# design.net
KiCad netlist of a schematic drawn in Altium Designer
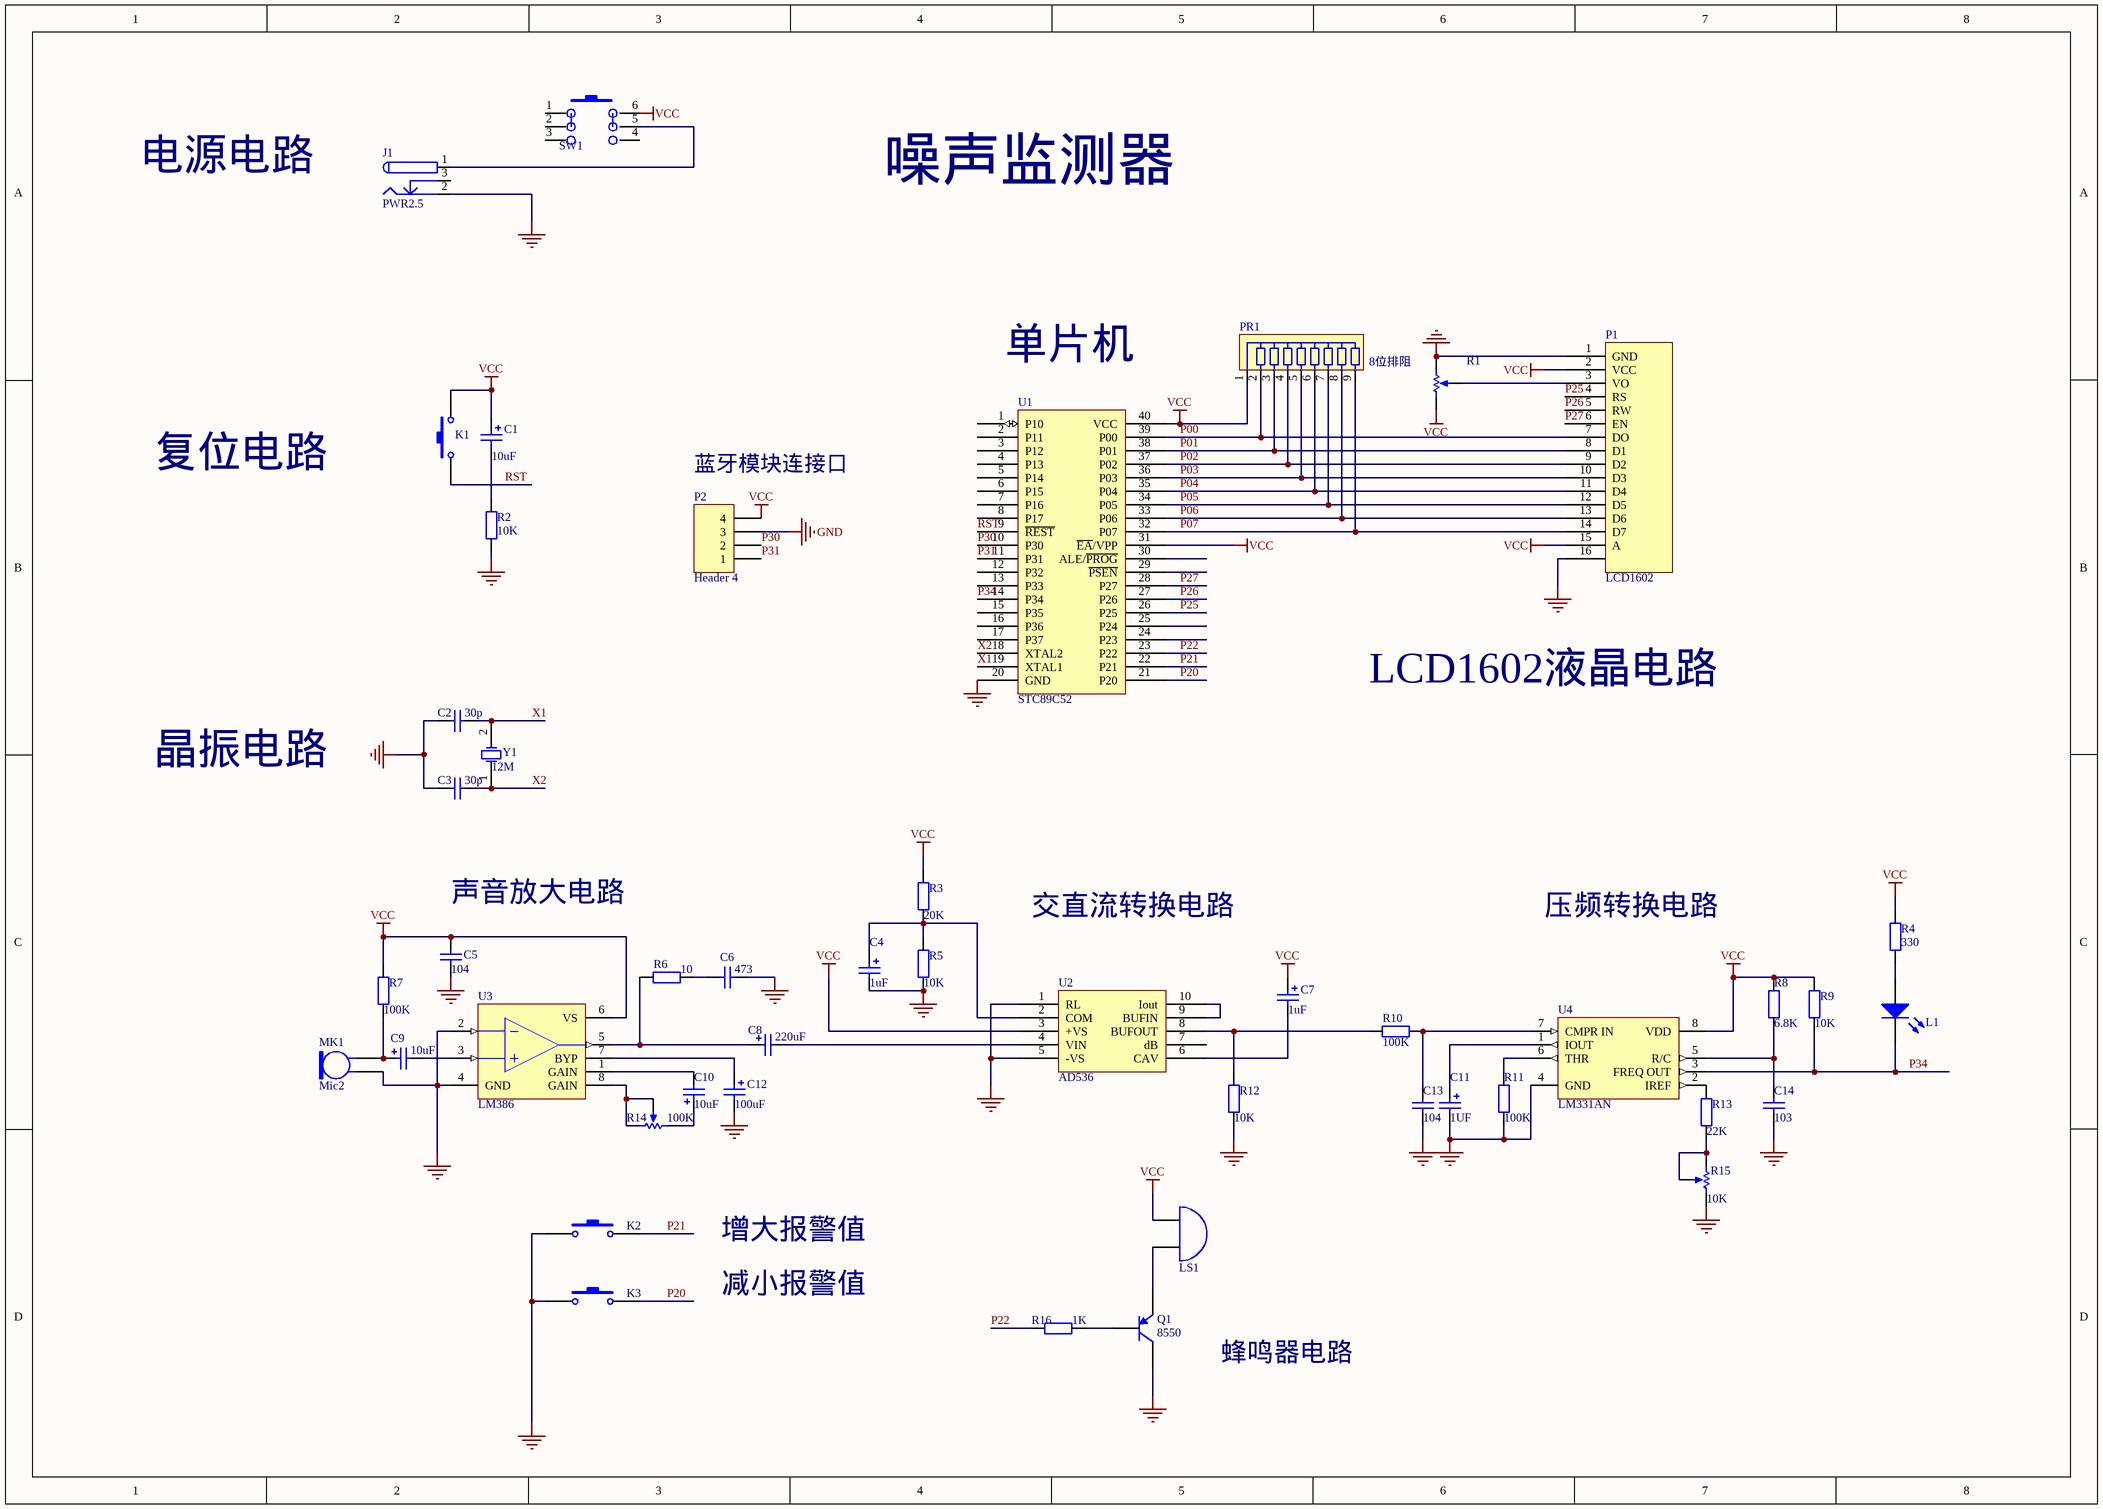
[diagram p0: 噪声监测器.SchDoc]

(export (version "E")
  (design (tool "Eeschema 10.0.6"))
  (components
    (comp (ref "C1") (value "10uF") (footprint "CAP2") (libsource (lib "*") (part "C+")))
    (comp (ref "C2") (value "30p") (footprint "CAPNORM") (libsource (lib "*") (part "CAP")))
    (comp (ref "C3") (value "30p") (footprint "CAPNORM") (libsource (lib "*") (part "CAP")))
    (comp (ref "C4") (value "1uF") (footprint "CAP3") (libsource (lib "*") (part "C+")))
    (comp (ref "C5") (value "104") (footprint "CAPNORM") (libsource (lib "*") (part "CAP")))
    (comp (ref "C6") (value "473") (footprint "CAPNORM") (libsource (lib "*") (part "CAP")))
    (comp (ref "C7") (value "1uF") (footprint "CAP3") (libsource (lib "*") (part "C+")))
    (comp (ref "C8") (value "220uF") (footprint "CAP4") (libsource (lib "*") (part "C+")))
    (comp (ref "C9") (value "10uF") (footprint "CAP2") (libsource (lib "*") (part "C+")))
    (comp (ref "C10") (value "10uF") (footprint "CAP2") (libsource (lib "*") (part "C+")))
    (comp (ref "C11") (value "1UF") (footprint "CAP2") (libsource (lib "*") (part "C+")))
    (comp (ref "C12") (value "100uF") (footprint "CAP3") (libsource (lib "*") (part "C+")))
    (comp (ref "C13") (value "104") (footprint "CAPNORM") (libsource (lib "*") (part "CAP")))
    (comp (ref "C14") (value "103") (footprint "CAPNORM") (libsource (lib "*") (part "CAP")))
    (comp (ref "J1")
      (value "PWR2.5")
      (footprint "PWR5V")
      (description "Low Voltage Power Supply Connector")
      (fields (field (name "PUBLISHER") "Altium Limited"))
      (libsource (lib "*") (part "PWR2.5"))
    )
    (comp (ref "K1") (value "SW-AJ") (footprint "KaiGuan") (libsource (lib "*") (part "SW-AJ")))
    (comp (ref "K2") (value "SW-AJ") (footprint "KaiGuan") (libsource (lib "*") (part "SW-AJ")))
    (comp (ref "K3") (value "SW-AJ") (footprint "KaiGuan") (libsource (lib "*") (part "SW-AJ")))
    (comp (ref "L1") (value "LED") (footprint "LED") (libsource (lib "*") (part "LED")))
    (comp (ref "LS1")
      (value "Bell")
      (footprint "FengMing")
      (description "Electrical Bell")
      (fields (field (name "MANUFACTURER") "Generic Components"))
      (libsource (lib "*") (part "Bell"))
    )
    (comp (ref "MK1")
      (value "Mic2")
      (footprint "MK1")
      (description "Microphone")
      (fields (field (name "PUBLISHER") "Altium Limited"))
      (libsource (lib "*") (part "Mic2"))
    )
    (comp (ref "P1") (value "LCD1602") (footprint "1602") (libsource (lib "*") (part "LCD1602")))
    (comp (ref "P2")
      (value "Header 4")
      (footprint "HT396K-4")
      (description "Header, 4-Pin")
      (fields (field (name "PUBLISHER") "Altium Limited"))
      (libsource (lib "01 Connect_IntegratedLibrary") (part "Header 4"))
    )
    (comp (ref "PR1") (value "8位排阻") (footprint "HDR1X9") (libsource (lib "*") (part "8位排阻")))
    (comp (ref "Q1")
      (value "8550")
      (footprint "SANJIGUAN")
      (description "PNP General Purpose Amplifier")
      (fields (field (name "PUBLISHER") "Altium Limited"))
      (libsource (lib "*") (part "2N3906"))
    )
    (comp (ref "R1")
      (value "~")
      (footprint "DIANWEIQI")
      (description "Potentiometer")
      (fields (field (name "PUBLISHER") "Altium Limited"))
      (libsource (lib "*") (part "RPot"))
    )
    (comp (ref "R2")
      (value "10K")
      (footprint "AXIAL-0.3")
      (description "Resistor")
      (fields (field (name "PUBLISHER") "Altium Limited"))
      (libsource (lib "") (part "Res2_1"))
    )
    (comp (ref "R3") (value "20K") (footprint "AXIAL-0.3") (libsource (lib "*") (part "RES0.4")))
    (comp (ref "R4")
      (value "330")
      (footprint "AXIAL-0.3")
      (description "Resistor")
      (fields (field (name "PUBLISHER") "Altium Limited"))
      (libsource (lib "*") (part "Res2"))
    )
    (comp (ref "R5") (value "10K") (footprint "AXIAL-0.3") (libsource (lib "*") (part "RES0.4")))
    (comp (ref "R6") (value "10") (footprint "AXIAL-0.3") (libsource (lib "") (part "RES0.4_1")))
    (comp (ref "R7") (value "100K") (footprint "AXIAL-0.3") (libsource (lib "") (part "RES0.4_2")))
    (comp (ref "R8") (value "6.8K") (footprint "AXIAL-0.3") (libsource (lib "") (part "电阻_2")))
    (comp (ref "R9") (value "10K") (footprint "AXIAL-0.3") (libsource (lib "") (part "电阻_1")))
    (comp (ref "R10") (value "100K") (footprint "AXIAL-0.3") (libsource (lib "*") (part "电阻")))
    (comp (ref "R11") (value "100K") (footprint "AXIAL-0.3") (libsource (lib "") (part "电阻_1")))
    (comp (ref "R12") (value "10K") (footprint "AXIAL-0.3") (libsource (lib "*") (part "RES0.4")))
    (comp (ref "R13") (value "22K") (footprint "AXIAL-0.3") (libsource (lib "") (part "电阻_2")))
    (comp (ref "R14")
      (value "100K")
      (footprint "Bianzuqi")
      (description "Potentiometer")
      (fields (field (name "PUBLISHER") "Altium Limited"))
      (libsource (lib "*") (part "RPot"))
    )
    (comp (ref "R15")
      (value "10K")
      (footprint "Bianzuqi")
      (description "Potentiometer")
      (fields (field (name "PUBLISHER") "Altium Limited"))
      (libsource (lib "*") (part "RPot"))
    )
    (comp (ref "R16")
      (value "1K")
      (footprint "AXIAL-0.3")
      (description "Resistor")
      (fields (field (name "PUBLISHER") "Altium Limited"))
      (libsource (lib "") (part "Res2_2"))
    )
    (comp (ref "SW1") (value "SW-6P") (footprint "SW-6P") (libsource (lib "6开关蜂鸣器电池等") (part "SW-6P")))
    (comp (ref "U1") (value "STC89C52") (footprint "52DANPIANJi") (libsource (lib "*") (part "AT89S52_1")))
    (comp (ref "U2") (value "AD536") (footprint "AD536") (libsource (lib "*") (part "AD536A")))
    (comp (ref "U3")
      (value "LM386")
      (footprint "LM386")
      (description "Low-Voltage Audio Power Amplifier")
      (fields (field (name "PUBLISHER") "Altium Limited"))
      (libsource (lib "*") (part "LM386M-1"))
    )
    (comp (ref "U4")
      (value "LM331AN")
      (footprint "LM331AN")
      (description "Precision Voltage-to-Frequency Converter")
      (fields (field (name "PUBLISHER") "Altium Limited"))
      (libsource (lib "*") (part "LM331AN"))
    )
    (comp (ref "Y1")
      (value "12M")
      (footprint "JINGZHEN")
      (description "Crystal Oscillator")
      (fields
        (field (name "MANUFACTURER") "Generic Components")
        (field (name "PUBLISHER") "Altium Hobart Technology Centre")
      )
      (libsource (lib "*") (part "XTAL"))
    )
  )
  (nets
    (net (code "1") (name "/P00") (class "Default")
      (node (ref "P1") (pin "7") (pinfunction "DO_7") (pintype "passive"))
      (node (ref "PR1") (pin "2") (pinfunction "2_2") (pintype "passive"))
      (node (ref "U1") (pin "39") (pinfunction "P00_39") (pintype "passive"))
    )
    (net (code "2") (name "/P01") (class "Default")
      (node (ref "P1") (pin "8") (pinfunction "D1_8") (pintype "passive"))
      (node (ref "PR1") (pin "3") (pinfunction "3_3") (pintype "passive"))
      (node (ref "U1") (pin "38") (pinfunction "P01_38") (pintype "passive"))
    )
    (net (code "3") (name "/P02") (class "Default")
      (node (ref "P1") (pin "9") (pinfunction "D2_9") (pintype "passive"))
      (node (ref "PR1") (pin "4") (pinfunction "4_4") (pintype "passive"))
      (node (ref "U1") (pin "37") (pinfunction "P02_37") (pintype "passive"))
    )
    (net (code "4") (name "/P03") (class "Default")
      (node (ref "P1") (pin "10") (pinfunction "D3_10") (pintype "passive"))
      (node (ref "PR1") (pin "5") (pinfunction "5_5") (pintype "passive"))
      (node (ref "U1") (pin "36") (pinfunction "P03_36") (pintype "passive"))
    )
    (net (code "5") (name "/P04") (class "Default")
      (node (ref "P1") (pin "11") (pinfunction "D4_11") (pintype "passive"))
      (node (ref "PR1") (pin "6") (pinfunction "6_6") (pintype "open_collector"))
      (node (ref "U1") (pin "35") (pinfunction "P04_35") (pintype "passive"))
    )
    (net (code "6") (name "/P05") (class "Default")
      (node (ref "P1") (pin "12") (pinfunction "D5_12") (pintype "passive"))
      (node (ref "PR1") (pin "7") (pinfunction "7_7") (pintype "passive"))
      (node (ref "U1") (pin "34") (pinfunction "P05_34") (pintype "passive"))
    )
    (net (code "7") (name "/P06") (class "Default")
      (node (ref "P1") (pin "13") (pinfunction "D6_13") (pintype "passive"))
      (node (ref "PR1") (pin "8") (pinfunction "8_8") (pintype "passive"))
      (node (ref "U1") (pin "33") (pinfunction "P06_33") (pintype "passive"))
    )
    (net (code "8") (name "/P07") (class "Default")
      (node (ref "P1") (pin "14") (pinfunction "D7_14") (pintype "passive"))
      (node (ref "PR1") (pin "9") (pinfunction "9_9") (pintype "passive"))
      (node (ref "U1") (pin "32") (pinfunction "P07_32") (pintype "passive"))
    )
    (net (code "9") (name "/P20") (class "Default")
      (node (ref "K3") (pin "2") (pinfunction "2_2") (pintype "passive"))
      (node (ref "U1") (pin "21") (pinfunction "P20_21") (pintype "passive"))
    )
    (net (code "10") (name "/P21") (class "Default")
      (node (ref "K2") (pin "2") (pinfunction "2_2") (pintype "passive"))
      (node (ref "U1") (pin "22") (pinfunction "P21_22") (pintype "passive"))
    )
    (net (code "11") (name "/P22") (class "Default")
      (node (ref "R16") (pin "1") (pinfunction "1_1") (pintype "passive"))
      (node (ref "U1") (pin "23") (pinfunction "P22_23") (pintype "passive"))
    )
    (net (code "12") (name "/P25") (class "Default")
      (node (ref "P1") (pin "4") (pinfunction "RS_4") (pintype "passive"))
      (node (ref "U1") (pin "26") (pinfunction "P25_26") (pintype "passive"))
    )
    (net (code "13") (name "/P26") (class "Default")
      (node (ref "P1") (pin "5") (pinfunction "RW_5") (pintype "passive"))
      (node (ref "U1") (pin "27") (pinfunction "P26_27") (pintype "passive"))
    )
    (net (code "14") (name "/P27") (class "Default")
      (node (ref "P1") (pin "6") (pinfunction "EN_6") (pintype "passive"))
      (node (ref "U1") (pin "28") (pinfunction "P27_28") (pintype "passive"))
    )
    (net (code "15") (name "/P30") (class "Default")
      (node (ref "P2") (pin "2") (pinfunction "2_2") (pintype "passive"))
      (node (ref "U1") (pin "10") (pinfunction "P30_10") (pintype "passive"))
    )
    (net (code "16") (name "/P31") (class "Default")
      (node (ref "P2") (pin "1") (pinfunction "1_1") (pintype "passive"))
      (node (ref "U1") (pin "11") (pinfunction "P31_11") (pintype "passive"))
    )
    (net (code "17") (name "/P34") (class "Default")
      (node (ref "L1") (pin "2") (pinfunction "K_2") (pintype "passive"))
      (node (ref "R9") (pin "1") (pinfunction "1_1") (pintype "passive"))
      (node (ref "U1") (pin "14") (pinfunction "P34_14") (pintype "passive"))
      (node (ref "U4") (pin "3") (pinfunction "FREQ_OUT_3") (pintype "output"))
    )
    (net (code "18") (name "/RST") (class "Default")
      (node (ref "K1") (pin "1") (pinfunction "1_1") (pintype "passive"))
      (node (ref "U1") (pin "9") (pinfunction "~{REST}_9") (pintype "passive"))
    )
    (net (code "19") (name "/X1") (class "Default")
      (node (ref "C2") (pin "2") (pinfunction "2_2") (pintype "passive"))
      (node (ref "U1") (pin "19") (pinfunction "XTAL1_19") (pintype "passive"))
      (node (ref "Y1") (pin "2") (pinfunction "OSC2_2") (pintype "passive"))
    )
    (net (code "20") (name "/X2") (class "Default")
      (node (ref "C3") (pin "2") (pinfunction "2_2") (pintype "passive"))
      (node (ref "U1") (pin "18") (pinfunction "XTAL2_18") (pintype "passive"))
      (node (ref "Y1") (pin "1") (pinfunction "OSC1_1") (pintype "passive"))
    )
    (net (code "21") (name "GND") (class "Default")
      (node (ref "C11") (pin "2") (pinfunction "2_2") (pintype "passive"))
      (node (ref "C12") (pin "2") (pinfunction "2_2") (pintype "passive"))
      (node (ref "C13") (pin "1") (pinfunction "1_1") (pintype "passive"))
      (node (ref "C14") (pin "1") (pinfunction "1_1") (pintype "passive"))
      (node (ref "C2") (pin "1") (pinfunction "1_1") (pintype "passive"))
      (node (ref "C3") (pin "1") (pinfunction "1_1") (pintype "passive"))
      (node (ref "C4") (pin "2") (pinfunction "2_2") (pintype "passive"))
      (node (ref "C5") (pin "1") (pinfunction "1_1") (pintype "passive"))
      (node (ref "C6") (pin "1") (pinfunction "1_1") (pintype "passive"))
      (node (ref "J1") (pin "2") (pinfunction "2_2") (pintype "power_in"))
      (node (ref "K2") (pin "1") (pinfunction "1_1") (pintype "passive"))
      (node (ref "K3") (pin "1") (pinfunction "1_1") (pintype "passive"))
      (node (ref "MK1") (pin "2") (pinfunction "2_2") (pintype "passive"))
      (node (ref "P1") (pin "1") (pinfunction "GND_1") (pintype "passive"))
      (node (ref "P1") (pin "16") (pinfunction "K_16") (pintype "passive"))
      (node (ref "P2") (pin "3") (pinfunction "3_3") (pintype "passive"))
      (node (ref "Q1") (pin "3") (pinfunction "C_3") (pintype "passive"))
      (node (ref "R1") (pin "3") (pinfunction "TAP_3") (pintype "passive"))
      (node (ref "R11") (pin "1") (pinfunction "1_1") (pintype "passive"))
      (node (ref "R12") (pin "2") (pinfunction "2_2") (pintype "passive"))
      (node (ref "R15") (pin "3") (pinfunction "TAP_3") (pintype "passive"))
      (node (ref "R2") (pin "1") (pinfunction "1_1") (pintype "passive"))
      (node (ref "R5") (pin "2") (pinfunction "2_2") (pintype "passive"))
      (node (ref "U1") (pin "20") (pinfunction "GND_20") (pintype "passive"))
      (node (ref "U2") (pin "1") (pinfunction "RL_1") (pintype "passive"))
      (node (ref "U2") (pin "5") (pinfunction "-VS_5") (pintype "passive"))
      (node (ref "U3") (pin "2") (pinfunction "IN-_2") (pintype "input"))
      (node (ref "U3") (pin "4") (pinfunction "GND_4") (pintype "power_in"))
      (node (ref "U4") (pin "4") (pinfunction "GND_4") (pintype "power_in"))
    )
    (net (code "22") (name "Net-(C1-Pad2)") (class "Default")
      (node (ref "C1") (pin "2") (pinfunction "2_2") (pintype "passive"))
      (node (ref "R2") (pin "2") (pinfunction "2_2") (pintype "passive"))
    )
    (net (code "23") (name "Net-(C6-Pad2)") (class "Default")
      (node (ref "C6") (pin "2") (pinfunction "2_2") (pintype "passive"))
      (node (ref "R6") (pin "1") (pinfunction "1_1") (pintype "passive"))
    )
    (net (code "24") (name "Net-(C9-Pad1)") (class "Default")
      (node (ref "C9") (pin "1") (pinfunction "1_1") (pintype "passive"))
      (node (ref "MK1") (pin "1") (pinfunction "1_1") (pintype "passive"))
      (node (ref "R7") (pin "1") (pinfunction "1_1") (pintype "passive"))
    )
    (net (code "25") (name "Net-(C10-Pad2)") (class "Default")
      (node (ref "C10") (pin "2") (pinfunction "2_2") (pintype "passive"))
      (node (ref "U3") (pin "1") (pinfunction "GAIN_1") (pintype "passive"))
    )
    (net (code "26") (name "Net-(J1-Pad1)") (class "Default")
      (node (ref "J1") (pin "1") (pinfunction "1_1") (pintype "power_in"))
      (node (ref "SW1") (pin "5") (pinfunction "5_5") (pintype "passive"))
    )
    (net (code "27") (name "Net-(L1-A)") (class "Default")
      (node (ref "L1") (pin "1") (pinfunction "A_1") (pintype "passive"))
      (node (ref "R4") (pin "2") (pinfunction "2_2") (pintype "passive"))
    )
    (net (code "28") (name "Net-(LS1-B)") (class "Default")
      (node (ref "LS1") (pin "2") (pinfunction "B_2") (pintype "passive"))
      (node (ref "Q1") (pin "1") (pinfunction "E_1") (pintype "passive"))
    )
    (net (code "29") (name "Net-(P1-VO)") (class "Default")
      (node (ref "P1") (pin "3") (pinfunction "VO_3") (pintype "passive"))
      (node (ref "R1") (pin "2") (pinfunction "BOT_2") (pintype "passive"))
    )
    (net (code "30") (name "Net-(Q1-B)") (class "Default")
      (node (ref "Q1") (pin "2") (pinfunction "B_2") (pintype "passive"))
      (node (ref "R16") (pin "2") (pinfunction "2_2") (pintype "passive"))
    )
    (net (code "31") (name "Net-(R14-BOT)") (class "Default")
      (node (ref "R14") (pin "2") (pinfunction "BOT_2") (pintype "passive"))
      (node (ref "R14") (pin "3") (pinfunction "TAP_3") (pintype "passive"))
      (node (ref "U3") (pin "8") (pinfunction "GAIN_8") (pintype "passive"))
    )
    (net (code "32") (name "Net-(R14-TOP)") (class "Default")
      (node (ref "C10") (pin "1") (pinfunction "1_1") (pintype "passive"))
      (node (ref "R14") (pin "1") (pinfunction "TOP_1") (pintype "passive"))
    )
    (net (code "33") (name "Net-(R15-BOT)") (class "Default")
      (node (ref "R13") (pin "2") (pinfunction "2_2") (pintype "passive"))
      (node (ref "R15") (pin "1") (pinfunction "TOP_1") (pintype "passive"))
      (node (ref "R15") (pin "2") (pinfunction "BOT_2") (pintype "passive"))
    )
    (net (code "34") (name "Net-(U2-BUFIN)") (class "Default")
      (node (ref "U2") (pin "10") (pinfunction "Iout_10") (pintype "passive"))
      (node (ref "U2") (pin "9") (pinfunction "BUFIN_9") (pintype "passive"))
    )
    (net (code "35") (name "Net-(U2-BUFOUT)") (class "Default")
      (node (ref "R10") (pin "1") (pinfunction "1_1") (pintype "passive"))
      (node (ref "R12") (pin "1") (pinfunction "1_1") (pintype "passive"))
      (node (ref "U2") (pin "8") (pinfunction "BUFOUT_8") (pintype "passive"))
    )
    (net (code "36") (name "Net-(U2-CAV)") (class "Default")
      (node (ref "C7") (pin "2") (pinfunction "2_2") (pintype "passive"))
      (node (ref "U2") (pin "6") (pinfunction "CAV_6") (pintype "passive"))
    )
    (net (code "37") (name "Net-(U2-COM)") (class "Default")
      (node (ref "C4") (pin "1") (pinfunction "1_1") (pintype "passive"))
      (node (ref "R3") (pin "2") (pinfunction "2_2") (pintype "passive"))
      (node (ref "R5") (pin "1") (pinfunction "1_1") (pintype "passive"))
      (node (ref "U2") (pin "2") (pinfunction "COM_2") (pintype "passive"))
    )
    (net (code "38") (name "Net-(U2-VIN)") (class "Default")
      (node (ref "C8") (pin "2") (pinfunction "2_2") (pintype "passive"))
      (node (ref "U2") (pin "4") (pinfunction "VIN_4") (pintype "passive"))
    )
    (net (code "39") (name "Net-(U3-BYP)") (class "Default")
      (node (ref "C12") (pin "1") (pinfunction "1_1") (pintype "passive"))
      (node (ref "U3") (pin "7") (pinfunction "BYP_7") (pintype "passive"))
    )
    (net (code "40") (name "Net-(U3-IN+)") (class "Default")
      (node (ref "C9") (pin "2") (pinfunction "2_2") (pintype "passive"))
      (node (ref "U3") (pin "3") (pinfunction "IN+_3") (pintype "input"))
    )
    (net (code "41") (name "Net-(U3-OUT)") (class "Default")
      (node (ref "C8") (pin "1") (pinfunction "1_1") (pintype "passive"))
      (node (ref "R6") (pin "2") (pinfunction "2_2") (pintype "passive"))
      (node (ref "U3") (pin "5") (pinfunction "OUT_5") (pintype "output"))
    )
    (net (code "42") (name "Net-(U4-CMPR_IN)") (class "Default")
      (node (ref "C13") (pin "2") (pinfunction "2_2") (pintype "passive"))
      (node (ref "R10") (pin "2") (pinfunction "2_2") (pintype "passive"))
      (node (ref "U4") (pin "7") (pinfunction "CMPR_IN_7") (pintype "input"))
    )
    (net (code "43") (name "Net-(U4-IOUT)") (class "Default")
      (node (ref "C11") (pin "1") (pinfunction "1_1") (pintype "passive"))
      (node (ref "U4") (pin "1") (pinfunction "IOUT_1") (pintype "output"))
    )
    (net (code "44") (name "Net-(U4-IREF)") (class "Default")
      (node (ref "R13") (pin "1") (pinfunction "1_1") (pintype "passive"))
      (node (ref "U4") (pin "2") (pinfunction "IREF_2") (pintype "output"))
    )
    (net (code "45") (name "Net-(U4-R{slash}C)") (class "Default")
      (node (ref "C14") (pin "2") (pinfunction "2_2") (pintype "passive"))
      (node (ref "R8") (pin "2") (pinfunction "2_2") (pintype "passive"))
      (node (ref "U4") (pin "5") (pinfunction "R/C_5") (pintype "output"))
    )
    (net (code "46") (name "Net-(U4-THR)") (class "Default")
      (node (ref "R11") (pin "2") (pinfunction "2_2") (pintype "passive"))
      (node (ref "U4") (pin "6") (pinfunction "THR_6") (pintype "output"))
    )
    (net (code "47") (name "VCC") (class "Default")
      (node (ref "C1") (pin "1") (pinfunction "1_1") (pintype "passive"))
      (node (ref "C5") (pin "2") (pinfunction "2_2") (pintype "passive"))
      (node (ref "C7") (pin "1") (pinfunction "1_1") (pintype "passive"))
      (node (ref "K1") (pin "2") (pinfunction "2_2") (pintype "passive"))
      (node (ref "LS1") (pin "1") (pinfunction "A_1") (pintype "passive"))
      (node (ref "P1") (pin "15") (pinfunction "A_15") (pintype "passive"))
      (node (ref "P1") (pin "2") (pinfunction "VCC_2") (pintype "passive"))
      (node (ref "P2") (pin "4") (pinfunction "4_4") (pintype "passive"))
      (node (ref "PR1") (pin "1") (pinfunction "1_1") (pintype "passive"))
      (node (ref "R1") (pin "1") (pinfunction "TOP_1") (pintype "passive"))
      (node (ref "R3") (pin "1") (pinfunction "1_1") (pintype "passive"))
      (node (ref "R4") (pin "1") (pinfunction "1_1") (pintype "passive"))
      (node (ref "R7") (pin "2") (pinfunction "2_2") (pintype "passive"))
      (node (ref "R8") (pin "1") (pinfunction "1_1") (pintype "passive"))
      (node (ref "R9") (pin "2") (pinfunction "2_2") (pintype "passive"))
      (node (ref "SW1") (pin "6") (pinfunction "7_6") (pintype "passive"))
      (node (ref "U1") (pin "31") (pinfunction "~{EA}/VPP_31") (pintype "passive"))
      (node (ref "U1") (pin "40") (pinfunction "VCC_40") (pintype "passive"))
      (node (ref "U2") (pin "3") (pinfunction "+VS_3") (pintype "passive"))
      (node (ref "U3") (pin "6") (pinfunction "VS_6") (pintype "power_in"))
      (node (ref "U4") (pin "8") (pinfunction "VDD_8") (pintype "power_in"))
    )
    (net (code "48") (name "unconnected-(J1-Pad3)") (class "Default")
      (node (ref "J1") (pin "3") (pinfunction "3_3") (pintype "power_in"))
    )
    (net (code "49") (name "unconnected-(SW1-Pad1)") (class "Default")
      (node (ref "SW1") (pin "1") (pinfunction "1_1") (pintype "passive"))
    )
    (net (code "50") (name "unconnected-(SW1-Pad2)") (class "Default")
      (node (ref "SW1") (pin "2") (pinfunction "2_2") (pintype "passive"))
    )
    (net (code "51") (name "unconnected-(SW1-Pad3)") (class "Default")
      (node (ref "SW1") (pin "3") (pinfunction "3_3") (pintype "passive"))
    )
    (net (code "52") (name "unconnected-(SW1-Pad4)") (class "Default")
      (node (ref "SW1") (pin "4") (pinfunction "4_4") (pintype "passive"))
    )
    (net (code "53") (name "unconnected-(U1-ALE{slash}~{PROG}-Pad30)") (class "Default")
      (node (ref "U1") (pin "30") (pinfunction "ALE/~{PROG}_30") (pintype "passive"))
    )
    (net (code "54") (name "unconnected-(U1-P10-Pad1)") (class "Default")
      (node (ref "U1") (pin "1") (pinfunction "P10_1") (pintype "bidirectional"))
    )
    (net (code "55") (name "unconnected-(U1-P11-Pad2)") (class "Default")
      (node (ref "U1") (pin "2") (pinfunction "P11_2") (pintype "passive"))
    )
    (net (code "56") (name "unconnected-(U1-P12-Pad3)") (class "Default")
      (node (ref "U1") (pin "3") (pinfunction "P12_3") (pintype "passive"))
    )
    (net (code "57") (name "unconnected-(U1-P13-Pad4)") (class "Default")
      (node (ref "U1") (pin "4") (pinfunction "P13_4") (pintype "passive"))
    )
    (net (code "58") (name "unconnected-(U1-P14-Pad5)") (class "Default")
      (node (ref "U1") (pin "5") (pinfunction "P14_5") (pintype "passive"))
    )
    (net (code "59") (name "unconnected-(U1-P15-Pad6)") (class "Default")
      (node (ref "U1") (pin "6") (pinfunction "P15_6") (pintype "passive"))
    )
    (net (code "60") (name "unconnected-(U1-P16-Pad7)") (class "Default")
      (node (ref "U1") (pin "7") (pinfunction "P16_7") (pintype "passive"))
    )
    (net (code "61") (name "unconnected-(U1-P17-Pad8)") (class "Default")
      (node (ref "U1") (pin "8") (pinfunction "P17_8") (pintype "passive"))
    )
    (net (code "62") (name "unconnected-(U1-P23-Pad24)") (class "Default")
      (node (ref "U1") (pin "24") (pinfunction "P23_24") (pintype "passive"))
    )
    (net (code "63") (name "unconnected-(U1-P24-Pad25)") (class "Default")
      (node (ref "U1") (pin "25") (pinfunction "P24_25") (pintype "passive"))
    )
    (net (code "64") (name "unconnected-(U1-P32-Pad12)") (class "Default")
      (node (ref "U1") (pin "12") (pinfunction "P32_12") (pintype "passive"))
    )
    (net (code "65") (name "unconnected-(U1-P33-Pad13)") (class "Default")
      (node (ref "U1") (pin "13") (pinfunction "P33_13") (pintype "passive"))
    )
    (net (code "66") (name "unconnected-(U1-P35-Pad15)") (class "Default")
      (node (ref "U1") (pin "15") (pinfunction "P35_15") (pintype "passive"))
    )
    (net (code "67") (name "unconnected-(U1-P36-Pad16)") (class "Default")
      (node (ref "U1") (pin "16") (pinfunction "P36_16") (pintype "passive"))
    )
    (net (code "68") (name "unconnected-(U1-P37-Pad17)") (class "Default")
      (node (ref "U1") (pin "17") (pinfunction "P37_17") (pintype "passive"))
    )
    (net (code "69") (name "unconnected-(U1-~{PSEN}-Pad29)") (class "Default")
      (node (ref "U1") (pin "29") (pinfunction "~{PSEN}_29") (pintype "passive"))
    )
    (net (code "70") (name "unconnected-(U2-dB-Pad7)") (class "Default")
      (node (ref "U2") (pin "7") (pinfunction "dB_7") (pintype "passive"))
    )
  )
)
